# mcu_io.net
KiCad netlist of a schematic drawn in Altium Designer
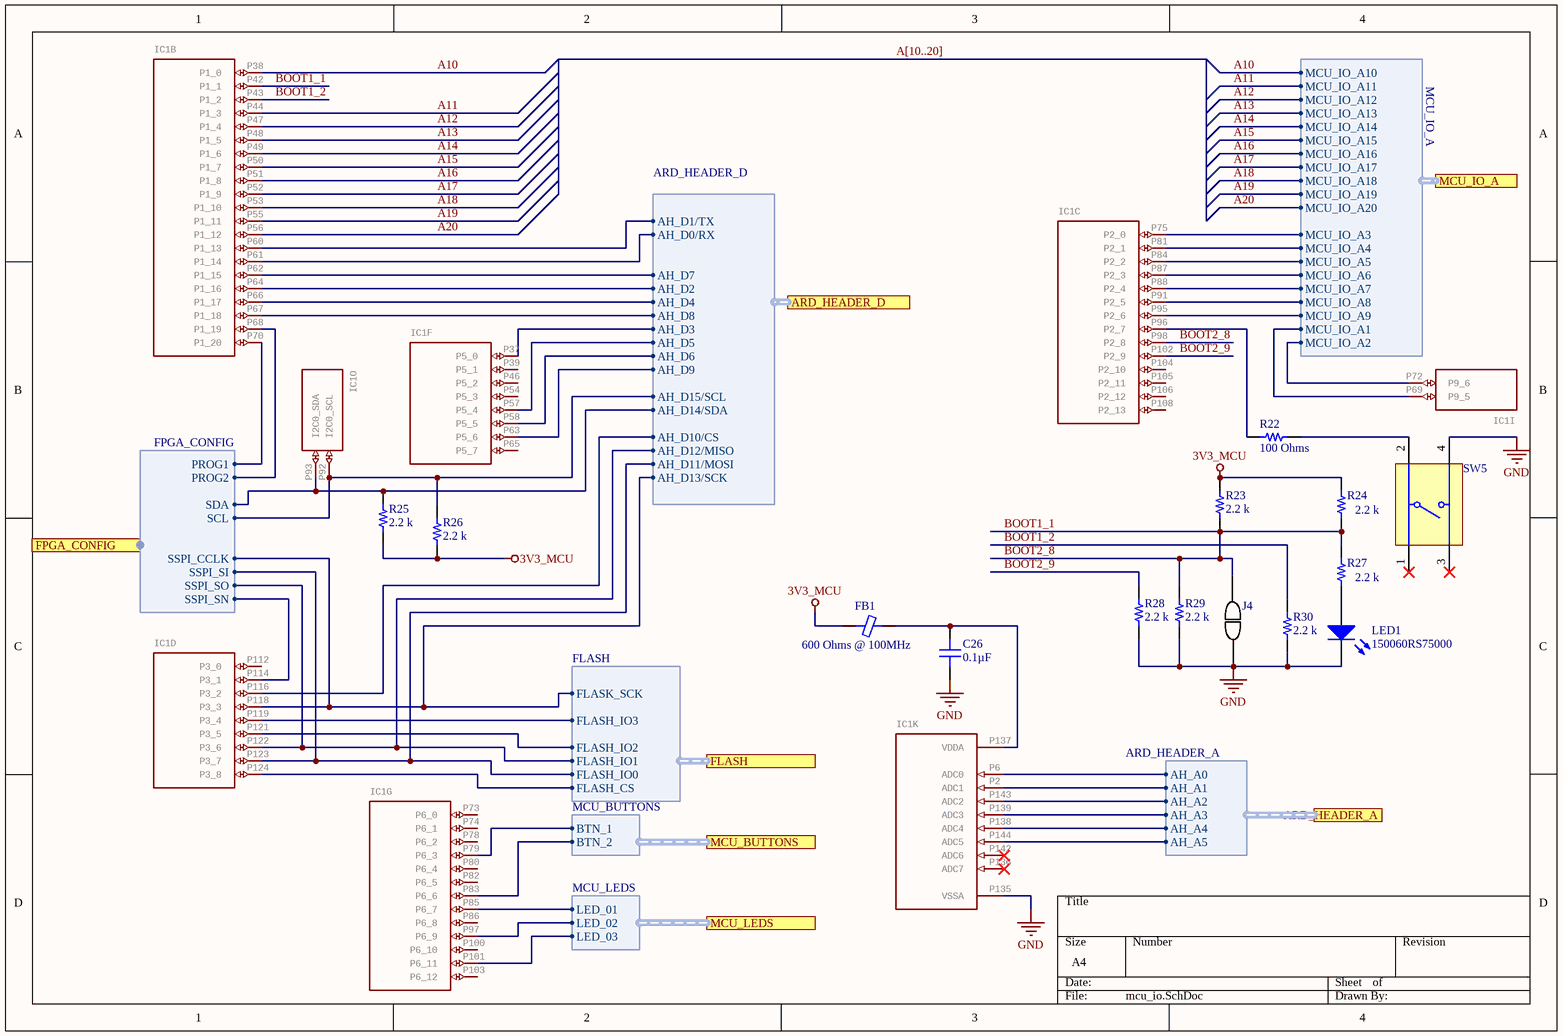
[diagram p0: mcu_io.SchDoc]

(export (version "E")
  (design (tool "Eeschema 10.0.6"))
  (components
    (comp (ref "C26")
      (value "0.1µF")
      (footprint "CAP 0603_1608")
      (description "CAP CER 0.1UF 50V X7R 0603")
      (fields (field (name "PART NUMBER") "C0603C104K5RAC7411") (field (name "MANUFACTURER") "KEMET"))
      (libsource (lib "Celestial Altium Library - altium_library (2)") (part "Capacitor"))
    )
    (comp (ref "FB1")
      (value "600 Ohms @ 100MHz")
      (footprint "FER 0603_1608")
      (description "FERRITE BEAD 600 OHM 0603 1LN")
      (fields
        (field (name "PART NUMBER") "BLM18AG601SN1D")
        (field (name "MANUFACTURER") "Murata Electronics")
      )
      (libsource (lib "Celestial Altium Library - altium_library (2)") (part "Ferrite Chip"))
    )
    (comp (ref "IC1")
      (value "LQFP144 - SOT486-1    LQFP144: plastic low profile quad flat package; 144 leads; body 20 x 20 x 1.4 mm    body + leads 22 x 22 mm   Solderland (pads) 0.4 x 1.5 mm on corners (8 x) and 0.28 x 1.5 mm (136 x)")
      (footprint "LQFP144")
      (libsource (lib "LPC4300") (part "LPC4300_LQFP144"))
    )
    (comp (ref "J4")
      (value "103185-2")
      (footprint "TE_103185-2")
      (description "02 MODII HDR SRST B/A .100CL")
      (libsource (lib "103185-2") (part "103185-2"))
    )
    (comp (ref "LED1")
      (value "150060RS75000")
      (footprint "0603_A")
      (description "SMD mono-color Chip LED, WL-SMCW, Red")
      (fields (field (name "MANUFACTURER") "Wuerth Elektronik"))
      (libsource (lib "Altium Content Vault") (part "WE-LED_K1A2-2"))
    )
    (comp (ref "R22")
      (value "100 Ohms")
      (footprint "RES 0603_1608")
      (description "RES 100 OHM 0.1% 1/16W 0603")
      (fields
        (field (name "PART NUMBER") "RNCS0603BKE100R")
        (field (name "MANUFACTURER") "Stackpole Electronics Inc")
      )
      (libsource (lib "Celestial Altium Library - altium_library (2)") (part "Resistor"))
    )
    (comp (ref "R23")
      (value "2.2 k")
      (footprint "RES 0603_1608")
      (description "RES SMD 2.2K OHM 1% 1/10W 0603")
      (fields
        (field (name "PART NUMBER") "ERJ-3EKF2201V")
        (field (name "MANUFACTURER") "Panasonic Electronic Components")
      )
      (libsource (lib "Celestial Altium Library - altium_library (2)") (part "Resistor"))
    )
    (comp (ref "R24")
      (value "2.2 k")
      (footprint "RES 0603_1608")
      (description "RES SMD 2.2K OHM 1% 1/10W 0603")
      (fields
        (field (name "PART NUMBER") "ERJ-3EKF2201V")
        (field (name "MANUFACTURER") "Panasonic Electronic Components")
      )
      (libsource (lib "Celestial Altium Library - altium_library (2)") (part "Resistor"))
    )
    (comp (ref "R25")
      (value "2.2 k")
      (footprint "RES 0603_1608")
      (description "RES 2.2K OHM 5% 1/10W 0603")
      (fields
        (field (name "PART NUMBER") "RK73B1JTTD222J")
        (field (name "MANUFACTURER") "KOA Speer Electronics, Inc.")
      )
      (libsource (lib "Celestial Altium Library - altium_library (2)") (part "Resistor"))
    )
    (comp (ref "R26")
      (value "2.2 k")
      (footprint "RES 0603_1608")
      (description "RES 2.2K OHM 5% 1/10W 0603")
      (fields
        (field (name "PART NUMBER") "RK73B1JTTD222J")
        (field (name "MANUFACTURER") "KOA Speer Electronics, Inc.")
      )
      (libsource (lib "Celestial Altium Library - altium_library (2)") (part "Resistor"))
    )
    (comp (ref "R27")
      (value "2.2 k")
      (footprint "RES 0603_1608")
      (description "RES SMD 2.2K OHM 1% 1/10W 0603")
      (fields
        (field (name "PART NUMBER") "ERJ-3EKF2201V")
        (field (name "MANUFACTURER") "Panasonic Electronic Components")
      )
      (libsource (lib "Celestial Altium Library - altium_library (2)") (part "Resistor"))
    )
    (comp (ref "R28")
      (value "2.2 k")
      (footprint "RES 0603_1608")
      (description "RES SMD 2.2K OHM 1% 1/10W 0603")
      (fields
        (field (name "PART NUMBER") "ERJ-3EKF2201V")
        (field (name "MANUFACTURER") "Panasonic Electronic Components")
      )
      (libsource (lib "Celestial Altium Library - altium_library (2)") (part "Resistor"))
    )
    (comp (ref "R29")
      (value "2.2 k")
      (footprint "RES 0603_1608")
      (description "RES SMD 2.2K OHM 1% 1/10W 0603")
      (fields
        (field (name "PART NUMBER") "ERJ-3EKF2201V")
        (field (name "MANUFACTURER") "Panasonic Electronic Components")
      )
      (libsource (lib "Celestial Altium Library - altium_library (2)") (part "Resistor"))
    )
    (comp (ref "R30")
      (value "2.2 k")
      (footprint "RES 0603_1608")
      (description "RES SMD 2.2K OHM 1% 1/10W 0603")
      (fields
        (field (name "PART NUMBER") "ERJ-3EKF2201V")
        (field (name "MANUFACTURER") "Panasonic Electronic Components")
      )
      (libsource (lib "Celestial Altium Library - altium_library (2)") (part "Resistor"))
    )
    (comp (ref "SW5")
      (value "FSM4JSMATR")
      (footprint "TECO-FSM4JSMATR_V")
      (description "Micro Miniature Push Button Switch FSM JSM, 50 mA, -35 to 85 degC, 4-Pin SMD, RoHS, Tape and Reel")
      (fields (field (name "MANUFACTURER") "TE Connectivity"))
      (libsource (lib "Altium Content Vault") (part "SW-SPST-4_A"))
    )
  )
  (nets
    (net (code "8") (name "/A10") (class "Default")
      (node (ref "IC1") (pin "P38") (pinfunction "P1_0_P38") (pintype "bidirectional"))
    )
    (net (code "9") (name "/A11") (class "Default")
      (node (ref "IC1") (pin "P44") (pinfunction "P1_3_P44") (pintype "bidirectional"))
    )
    (net (code "10") (name "/A12") (class "Default")
      (node (ref "IC1") (pin "P47") (pinfunction "P1_4_P47") (pintype "bidirectional"))
    )
    (net (code "11") (name "/A13") (class "Default")
      (node (ref "IC1") (pin "P48") (pinfunction "P1_5_P48") (pintype "bidirectional"))
    )
    (net (code "12") (name "/A14") (class "Default")
      (node (ref "IC1") (pin "P49") (pinfunction "P1_6_P49") (pintype "bidirectional"))
    )
    (net (code "13") (name "/A15") (class "Default")
      (node (ref "IC1") (pin "P50") (pinfunction "P1_7_P50") (pintype "bidirectional"))
    )
    (net (code "14") (name "/A16") (class "Default")
      (node (ref "IC1") (pin "P51") (pinfunction "P1_8_P51") (pintype "bidirectional"))
    )
    (net (code "15") (name "/A17") (class "Default")
      (node (ref "IC1") (pin "P52") (pinfunction "P1_9_P52") (pintype "bidirectional"))
    )
    (net (code "16") (name "/A18") (class "Default")
      (node (ref "IC1") (pin "P53") (pinfunction "P1_10_P53") (pintype "bidirectional"))
    )
    (net (code "17") (name "/A19") (class "Default")
      (node (ref "IC1") (pin "P55") (pinfunction "P1_11_P55") (pintype "bidirectional"))
    )
    (net (code "18") (name "/A20") (class "Default")
      (node (ref "IC1") (pin "P56") (pinfunction "P1_12_P56") (pintype "bidirectional"))
    )
    (net (code "19") (name "/AH_A0") (class "Default")
      (node (ref "IC1") (pin "P6") (pinfunction "ADC0_P6") (pintype "input"))
    )
    (net (code "20") (name "/AH_A1") (class "Default")
      (node (ref "IC1") (pin "P2") (pinfunction "ADC1_P2") (pintype "input"))
    )
    (net (code "21") (name "/AH_A2") (class "Default")
      (node (ref "IC1") (pin "P143") (pinfunction "ADC2_P143") (pintype "input"))
    )
    (net (code "22") (name "/AH_A3") (class "Default")
      (node (ref "IC1") (pin "P139") (pinfunction "ADC3_P139") (pintype "input"))
    )
    (net (code "23") (name "/AH_A4") (class "Default")
      (node (ref "IC1") (pin "P138") (pinfunction "ADC4_P138") (pintype "input"))
    )
    (net (code "24") (name "/AH_A5") (class "Default")
      (node (ref "IC1") (pin "P144") (pinfunction "ADC5_P144") (pintype "input"))
    )
    (net (code "25") (name "/AH_D0{slash}RX") (class "Default")
      (node (ref "IC1") (pin "P61") (pinfunction "P1_14_P61") (pintype "bidirectional"))
    )
    (net (code "26") (name "/AH_D1{slash}TX") (class "Default")
      (node (ref "IC1") (pin "P60") (pinfunction "P1_13_P60") (pintype "bidirectional"))
    )
    (net (code "27") (name "/AH_D2") (class "Default")
      (node (ref "IC1") (pin "P64") (pinfunction "P1_16_P64") (pintype "bidirectional"))
    )
    (net (code "28") (name "/AH_D3") (class "Default")
      (node (ref "IC1") (pin "P37") (pinfunction "P5_0_P37") (pintype "bidirectional"))
    )
    (net (code "29") (name "/AH_D4") (class "Default")
      (node (ref "IC1") (pin "P66") (pinfunction "P1_17_P66") (pintype "bidirectional"))
    )
    (net (code "30") (name "/AH_D5") (class "Default")
      (node (ref "IC1") (pin "P57") (pinfunction "P5_4_P57") (pintype "bidirectional"))
    )
    (net (code "31") (name "/AH_D6") (class "Default")
      (node (ref "IC1") (pin "P58") (pinfunction "P5_5_P58") (pintype "bidirectional"))
    )
    (net (code "32") (name "/AH_D7") (class "Default")
      (node (ref "IC1") (pin "P62") (pinfunction "P1_15_P62") (pintype "bidirectional"))
    )
    (net (code "33") (name "/AH_D8") (class "Default")
      (node (ref "IC1") (pin "P67") (pinfunction "P1_18_P67") (pintype "bidirectional"))
    )
    (net (code "34") (name "/AH_D9") (class "Default")
      (node (ref "IC1") (pin "P63") (pinfunction "P5_6_P63") (pintype "bidirectional"))
    )
    (net (code "35") (name "/AH_D10{slash}CS") (class "Default")
      (node (ref "IC1") (pin "P116") (pinfunction "P3_2_P116") (pintype "bidirectional"))
    )
    (net (code "36") (name "/AH_D11{slash}MOSI") (class "Default")
      (node (ref "IC1") (pin "P123") (pinfunction "P3_7_P123") (pintype "bidirectional"))
    )
    (net (code "37") (name "/AH_D12{slash}MISO") (class "Default")
      (node (ref "IC1") (pin "P122") (pinfunction "P3_6_P122") (pintype "bidirectional"))
    )
    (net (code "38") (name "/AH_D13{slash}SCK") (class "Default")
      (node (ref "IC1") (pin "P118") (pinfunction "P3_3_P118") (pintype "bidirectional"))
    )
    (net (code "39") (name "/AH_D14{slash}SDA") (class "Default")
      (node (ref "IC1") (pin "P93") (pinfunction "I2C0_SDA_P93") (pintype "bidirectional"))
      (node (ref "R25") (pin "1") (pinfunction "1_1") (pintype "passive"))
    )
    (net (code "40") (name "/AH_D15{slash}SCL") (class "Default")
      (node (ref "IC1") (pin "P92") (pinfunction "I2C0_SCL_P92") (pintype "bidirectional"))
      (node (ref "R26") (pin "1") (pinfunction "1_1") (pintype "passive"))
    )
    (net (code "42") (name "/BOOT1_1") (class "Default")
      (node (ref "IC1") (pin "P42") (pinfunction "P1_1_P42") (pintype "bidirectional"))
      (node (ref "IC1") (pin "P98") (pinfunction "P2_8_P98") (pintype "bidirectional"))
      (node (ref "J4") (pin "2") (pinfunction "2_2") (pintype "passive"))
      (node (ref "R23") (pin "1") (pinfunction "1_1") (pintype "passive"))
      (node (ref "R24") (pin "1") (pinfunction "1_1") (pintype "passive"))
      (node (ref "R27") (pin "2") (pinfunction "2_2") (pintype "passive"))
      (node (ref "R29") (pin "2") (pinfunction "2_2") (pintype "passive"))
    )
    (net (code "43") (name "/BOOT1_2") (class "Default")
      (node (ref "IC1") (pin "P43") (pinfunction "P1_2_P43") (pintype "bidirectional"))
      (node (ref "R30") (pin "2") (pinfunction "2_2") (pintype "passive"))
    )
    (net (code "44") (name "/BOOT2_9") (class "Default")
      (node (ref "IC1") (pin "P102") (pinfunction "P2_9_P102") (pintype "bidirectional"))
      (node (ref "R28") (pin "2") (pinfunction "2_2") (pintype "passive"))
    )
    (net (code "45") (name "/BTN_1") (class "Default")
      (node (ref "IC1") (pin "P79") (pinfunction "P6_3_P79") (pintype "bidirectional"))
    )
    (net (code "46") (name "/BTN_2") (class "Default")
      (node (ref "IC1") (pin "P83") (pinfunction "P6_6_P83") (pintype "bidirectional"))
    )
    (net (code "47") (name "/FLASH_CS") (class "Default")
      (node (ref "IC1") (pin "P124") (pinfunction "P3_8_P124") (pintype "bidirectional"))
    )
    (net (code "48") (name "/FLASH_IO2") (class "Default")
      (node (ref "IC1") (pin "P121") (pinfunction "P3_5_P121") (pintype "bidirectional"))
    )
    (net (code "49") (name "/FLASH_IO3") (class "Default")
      (node (ref "IC1") (pin "P119") (pinfunction "P3_4_P119") (pintype "bidirectional"))
    )
    (net (code "50") (name "/LED_01") (class "Default")
      (node (ref "IC1") (pin "P85") (pinfunction "P6_7_P85") (pintype "bidirectional"))
    )
    (net (code "51") (name "/LED_02") (class "Default")
      (node (ref "IC1") (pin "P97") (pinfunction "P6_9_P97") (pintype "bidirectional"))
    )
    (net (code "52") (name "/LED_03") (class "Default")
      (node (ref "IC1") (pin "P101") (pinfunction "P6_11_P101") (pintype "bidirectional"))
    )
    (net (code "53") (name "/MCU_IO_A1") (class "Default")
      (node (ref "IC1") (pin "P69") (pinfunction "P9_5_P69") (pintype "bidirectional"))
    )
    (net (code "54") (name "/MCU_IO_A2") (class "Default")
      (node (ref "IC1") (pin "P72") (pinfunction "P9_6_P72") (pintype "bidirectional"))
    )
    (net (code "55") (name "/MCU_IO_A3") (class "Default")
      (node (ref "IC1") (pin "P75") (pinfunction "P2_0_P75") (pintype "bidirectional"))
    )
    (net (code "56") (name "/MCU_IO_A4") (class "Default")
      (node (ref "IC1") (pin "P81") (pinfunction "P2_1_P81") (pintype "bidirectional"))
    )
    (net (code "57") (name "/MCU_IO_A5") (class "Default")
      (node (ref "IC1") (pin "P84") (pinfunction "P2_2_P84") (pintype "bidirectional"))
    )
    (net (code "58") (name "/MCU_IO_A6") (class "Default")
      (node (ref "IC1") (pin "P87") (pinfunction "P2_3_P87") (pintype "bidirectional"))
    )
    (net (code "59") (name "/MCU_IO_A7") (class "Default")
      (node (ref "IC1") (pin "P88") (pinfunction "P2_4_P88") (pintype "bidirectional"))
    )
    (net (code "60") (name "/MCU_IO_A8") (class "Default")
      (node (ref "IC1") (pin "P91") (pinfunction "P2_5_P91") (pintype "bidirectional"))
    )
    (net (code "61") (name "/MCU_IO_A9") (class "Default")
      (node (ref "IC1") (pin "P95") (pinfunction "P2_6_P95") (pintype "bidirectional"))
    )
    (net (code "62") (name "/PROG1") (class "Default")
      (node (ref "IC1") (pin "P70") (pinfunction "P1_20_P70") (pintype "bidirectional"))
    )
    (net (code "63") (name "/PROG2") (class "Default")
      (node (ref "IC1") (pin "P68") (pinfunction "P1_19_P68") (pintype "bidirectional"))
    )
    (net (code "64") (name "/SSPI_SN") (class "Default")
      (node (ref "IC1") (pin "P114") (pinfunction "P3_1_P114") (pintype "bidirectional"))
    )
    (net (code "72") (name "3V3_MCU") (class "Default")
      (node (ref "FB1") (pin "1") (pinfunction "1_1") (pintype "passive"))
      (node (ref "R23") (pin "2") (pinfunction "2_2") (pintype "passive"))
      (node (ref "R24") (pin "2") (pinfunction "2_2") (pintype "passive"))
      (node (ref "R25") (pin "2") (pinfunction "2_2") (pintype "passive"))
      (node (ref "R26") (pin "2") (pinfunction "2_2") (pintype "passive"))
    )
    (net (code "73") (name "GND") (class "Default")
      (node (ref "C26") (pin "1") (pinfunction "1_1") (pintype "passive"))
      (node (ref "IC1") (pin "P135") (pinfunction "VSSA_P135") (pintype "power_in"))
      (node (ref "J4") (pin "1") (pinfunction "1_1") (pintype "passive"))
      (node (ref "LED1") (pin "1") (pinfunction "K_1") (pintype "passive"))
      (node (ref "R28") (pin "1") (pinfunction "1_1") (pintype "passive"))
      (node (ref "R29") (pin "1") (pinfunction "1_1") (pintype "passive"))
      (node (ref "R30") (pin "1") (pinfunction "1_1") (pintype "passive"))
      (node (ref "SW5") (pin "4") (pinfunction "4_4") (pintype "passive"))
    )
    (net (code "74") (name "Net-(IC1C-P2_7)") (class "Default")
      (node (ref "IC1") (pin "P96") (pinfunction "P2_7_P96") (pintype "bidirectional"))
      (node (ref "R22") (pin "1") (pinfunction "1_1") (pintype "passive"))
    )
    (net (code "75") (name "Net-(IC1K-VDDA)") (class "Default")
      (node (ref "C26") (pin "2") (pinfunction "2_2") (pintype "passive"))
      (node (ref "FB1") (pin "2") (pinfunction "2_2") (pintype "passive"))
      (node (ref "IC1") (pin "P137") (pinfunction "VDDA_P137") (pintype "power_in"))
    )
    (net (code "76") (name "Net-(LED1-A)") (class "Default")
      (node (ref "LED1") (pin "2") (pinfunction "A_2") (pintype "passive"))
      (node (ref "R27") (pin "1") (pinfunction "1_1") (pintype "passive"))
    )
    (net (code "77") (name "Net-(R22-Pad2)") (class "Default")
      (node (ref "R22") (pin "2") (pinfunction "2_2") (pintype "passive"))
      (node (ref "SW5") (pin "2") (pinfunction "2_2") (pintype "passive"))
    )
    (net (code "78") (name "unconnected-(IC1C-P2_10-PadP104)") (class "Default")
      (node (ref "IC1") (pin "P104") (pinfunction "P2_10_P104") (pintype "bidirectional"))
    )
    (net (code "79") (name "unconnected-(IC1C-P2_11-PadP105)") (class "Default")
      (node (ref "IC1") (pin "P105") (pinfunction "P2_11_P105") (pintype "bidirectional"))
    )
    (net (code "80") (name "unconnected-(IC1C-P2_12-PadP106)") (class "Default")
      (node (ref "IC1") (pin "P106") (pinfunction "P2_12_P106") (pintype "bidirectional"))
    )
    (net (code "81") (name "unconnected-(IC1C-P2_13-PadP108)") (class "Default")
      (node (ref "IC1") (pin "P108") (pinfunction "P2_13_P108") (pintype "bidirectional"))
    )
    (net (code "82") (name "unconnected-(IC1D-P3_0-PadP112)") (class "Default")
      (node (ref "IC1") (pin "P112") (pinfunction "P3_0_P112") (pintype "bidirectional"))
    )
    (net (code "83") (name "unconnected-(IC1F-P5_1-PadP39)") (class "Default")
      (node (ref "IC1") (pin "P39") (pinfunction "P5_1_P39") (pintype "bidirectional"))
    )
    (net (code "84") (name "unconnected-(IC1F-P5_2-PadP46)") (class "Default")
      (node (ref "IC1") (pin "P46") (pinfunction "P5_2_P46") (pintype "bidirectional"))
    )
    (net (code "85") (name "unconnected-(IC1F-P5_3-PadP54)") (class "Default")
      (node (ref "IC1") (pin "P54") (pinfunction "P5_3_P54") (pintype "bidirectional"))
    )
    (net (code "86") (name "unconnected-(IC1F-P5_7-PadP65)") (class "Default")
      (node (ref "IC1") (pin "P65") (pinfunction "P5_7_P65") (pintype "bidirectional"))
    )
    (net (code "87") (name "unconnected-(IC1G-P6_0-PadP73)") (class "Default")
      (node (ref "IC1") (pin "P73") (pinfunction "P6_0_P73") (pintype "bidirectional"))
    )
    (net (code "88") (name "unconnected-(IC1G-P6_1-PadP74)") (class "Default")
      (node (ref "IC1") (pin "P74") (pinfunction "P6_1_P74") (pintype "bidirectional"))
    )
    (net (code "89") (name "unconnected-(IC1G-P6_2-PadP78)") (class "Default")
      (node (ref "IC1") (pin "P78") (pinfunction "P6_2_P78") (pintype "bidirectional"))
    )
    (net (code "90") (name "unconnected-(IC1G-P6_4-PadP80)") (class "Default")
      (node (ref "IC1") (pin "P80") (pinfunction "P6_4_P80") (pintype "bidirectional"))
    )
    (net (code "91") (name "unconnected-(IC1G-P6_5-PadP82)") (class "Default")
      (node (ref "IC1") (pin "P82") (pinfunction "P6_5_P82") (pintype "bidirectional"))
    )
    (net (code "92") (name "unconnected-(IC1G-P6_8-PadP86)") (class "Default")
      (node (ref "IC1") (pin "P86") (pinfunction "P6_8_P86") (pintype "bidirectional"))
    )
    (net (code "93") (name "unconnected-(IC1G-P6_10-PadP100)") (class "Default")
      (node (ref "IC1") (pin "P100") (pinfunction "P6_10_P100") (pintype "bidirectional"))
    )
    (net (code "94") (name "unconnected-(IC1G-P6_12-PadP103)") (class "Default")
      (node (ref "IC1") (pin "P103") (pinfunction "P6_12_P103") (pintype "bidirectional"))
    )
    (net (code "95") (name "unconnected-(IC1K-ADC6-PadP142)") (class "Default")
      (node (ref "IC1") (pin "P142") (pinfunction "ADC6_P142") (pintype "input+no_connect"))
    )
    (net (code "96") (name "unconnected-(IC1K-ADC7-PadP136)") (class "Default")
      (node (ref "IC1") (pin "P136") (pinfunction "ADC7_P136") (pintype "input+no_connect"))
    )
    (net (code "97") (name "unconnected-(SW5-Pad1)") (class "Default")
      (node (ref "SW5") (pin "1") (pinfunction "1_1") (pintype "passive+no_connect"))
    )
    (net (code "98") (name "unconnected-(SW5-Pad3)") (class "Default")
      (node (ref "SW5") (pin "3") (pinfunction "3_3") (pintype "passive+no_connect"))
    )
  )
)
